# BTN7971b.net
KiCad netlist of a schematic drawn in Altium Designer
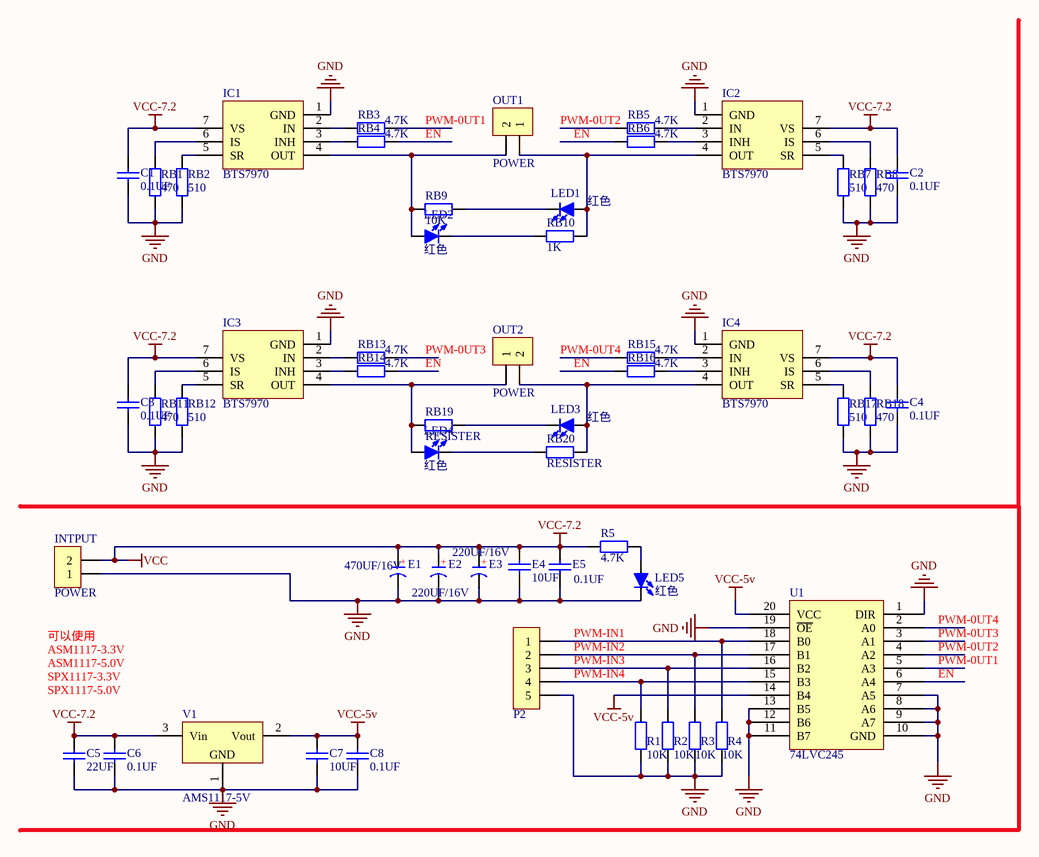
[diagram p0: BTN7971b.SchDoc]

(export (version "E")
  (design (tool "Eeschema 10.0.6"))
  (components
    (comp (ref "C1") (value "0.1UF") (footprint "R/C 0805") (libsource (lib "Schlib1") (part "CAP")))
    (comp (ref "C2") (value "0.1UF") (footprint "R/C 0805") (libsource (lib "Schlib1") (part "CAP")))
    (comp (ref "C3") (value "0.1UF") (footprint "R/C 0805") (libsource (lib "Schlib1") (part "CAP")))
    (comp (ref "C4") (value "0.1UF") (footprint "R/C 0805") (libsource (lib "Schlib1") (part "CAP")))
    (comp (ref "C5") (value "22UF") (footprint "R/C 0805") (libsource (lib "Schlib1") (part "CAP")))
    (comp (ref "C6") (value "0.1UF") (footprint "R/C 0805") (libsource (lib "Schlib1") (part "CAP")))
    (comp (ref "C7") (value "10UF") (footprint "R/C 0805") (libsource (lib "Schlib1") (part "CAP")))
    (comp (ref "C8") (value "0.1UF") (footprint "R/C 0805") (libsource (lib "Schlib1") (part "CAP")))
    (comp (ref "E1")
      (value "470UF/16V")
      (footprint "CM E(8*10.2)")
      (description "贴片电解电容")
      (fields (field (name "版权归属") "源创客"))
      (libsource (lib "3.1   - 电阻-电容-电感") (part "C-CM"))
    )
    (comp (ref "E2")
      (value "220UF/16V")
      (footprint "CM D(6.3*7.7)")
      (description "贴片电解电容")
      (fields (field (name "版权归属") "源创客"))
      (libsource (lib "3.1   - 电阻-电容-电感") (part "C-CM"))
    )
    (comp (ref "E3")
      (value "220UF/16V")
      (footprint "CM D(6.3*7.7)")
      (description "贴片电解电容")
      (fields (field (name "版权归属") "源创客"))
      (libsource (lib "3.1   - 电阻-电容-电感") (part "C-CM"))
    )
    (comp (ref "E4") (value "10UF") (footprint "R/C 0805") (libsource (lib "Schlib1") (part "CAP")))
    (comp (ref "E5") (value "0.1UF") (footprint "R/C 0805") (libsource (lib "Schlib1") (part "CAP")))
    (comp (ref "IC1")
      (value "BTS7970")
      (footprint "TO263-7A")
      (description "电机驱动芯片")
      (fields (field (name "版权归属") "源创客"))
      (libsource (lib "1.1   - IC芯片") (part "BTS7970"))
    )
    (comp (ref "IC2")
      (value "BTS7970")
      (footprint "TO263-7A")
      (description "电机驱动芯片")
      (fields (field (name "版权归属") "源创客"))
      (libsource (lib "") (part "BTS7970_1"))
    )
    (comp (ref "IC3")
      (value "BTS7970")
      (footprint "TO263-7A")
      (description "电机驱动芯片")
      (fields (field (name "版权归属") "源创客"))
      (libsource (lib "1.1   - IC芯片") (part "BTS7970"))
    )
    (comp (ref "IC4")
      (value "BTS7970")
      (footprint "TO263-7A")
      (description "电机驱动芯片")
      (fields (field (name "版权归属") "源创客"))
      (libsource (lib "") (part "BTS7970_1"))
    )
    (comp (ref "INTPUT") (value "POWER") (footprint "XT30") (libsource (lib "") (part "Header 2 L_2")))
    (comp (ref "LED1")
      (value "红色")
      (footprint "LED 0805R")
      (description "贴片LED")
      (fields (field (name "版权归属") "源创客"))
      (libsource (lib "3.6   - LED") (part "LED-SMD"))
    )
    (comp (ref "LED2")
      (value "红色")
      (footprint "LED 0805R")
      (description "贴片LED")
      (fields (field (name "版权归属") "源创客"))
      (libsource (lib "3.6   - LED") (part "LED-SMD"))
    )
    (comp (ref "LED3")
      (value "红色")
      (footprint "LED 0805R")
      (description "贴片LED")
      (fields (field (name "版权归属") "源创客"))
      (libsource (lib "3.6   - LED") (part "LED-SMD"))
    )
    (comp (ref "LED4")
      (value "红色")
      (footprint "LED 0805R")
      (description "贴片LED")
      (fields (field (name "版权归属") "源创客"))
      (libsource (lib "3.6   - LED") (part "LED-SMD"))
    )
    (comp (ref "LED5")
      (value "红色")
      (footprint "LED 0805R")
      (description "贴片LED")
      (fields (field (name "版权归属") "源创客"))
      (libsource (lib "3.6   - LED") (part "LED-SMD"))
    )
    (comp (ref "OUT1") (value "POWER") (footprint "XT30") (libsource (lib "双路BTN电机驱动") (part "Header 2 L")))
    (comp (ref "OUT2") (value "POWER") (footprint "XT30") (libsource (lib "") (part "Header 2 L_1")))
    (comp (ref "P2")
      (value "HDR-1X5")
      (footprint "XH2.54-LI-5P")
      (description "5P接插件")
      (fields (field (name "版权归属") "源创客"))
      (libsource (lib "4.5   - 接插件-脚距2.54") (part "Header 5"))
    )
    (comp (ref "R1") (value "10K") (footprint "R/C 0805") (libsource (lib "Schlib1") (part "RESISTER")))
    (comp (ref "R2") (value "10K") (footprint "R/C 0805") (libsource (lib "Schlib1") (part "RESISTER")))
    (comp (ref "R3") (value "10K") (footprint "R/C 0805") (libsource (lib "Schlib1") (part "RESISTER")))
    (comp (ref "R4") (value "10K") (footprint "R/C 0805") (libsource (lib "Schlib1") (part "RESISTER")))
    (comp (ref "R5") (value "4.7K") (footprint "R/C 0805") (libsource (lib "") (part "RESISTER_1")))
    (comp (ref "RB1") (value "470") (footprint "R/C 0805") (libsource (lib "Schlib1") (part "RESISTER")))
    (comp (ref "RB2") (value "510") (footprint "R/C 0805") (libsource (lib "Schlib1") (part "RESISTER")))
    (comp (ref "RB3") (value "4.7K") (footprint "R/C 0805") (libsource (lib "") (part "RESISTER_1")))
    (comp (ref "RB4") (value "4.7K") (footprint "R/C 0805") (libsource (lib "") (part "RESISTER_1")))
    (comp (ref "RB5") (value "4.7K") (footprint "R/C 0805") (libsource (lib "") (part "RESISTER_1")))
    (comp (ref "RB6") (value "4.7K") (footprint "R/C 0805") (libsource (lib "") (part "RESISTER_1")))
    (comp (ref "RB7") (value "510") (footprint "R/C 0805") (libsource (lib "Schlib1") (part "RESISTER")))
    (comp (ref "RB8") (value "470") (footprint "R/C 0805") (libsource (lib "Schlib1") (part "RESISTER")))
    (comp (ref "RB9") (value "10K") (footprint "R/C 0805") (libsource (lib "") (part "RESISTER_2")))
    (comp (ref "RB10") (value "1K") (footprint "R/C 0805") (libsource (lib "") (part "RESISTER_2")))
    (comp (ref "RB11") (value "470") (footprint "R/C 0805") (libsource (lib "Schlib1") (part "RESISTER")))
    (comp (ref "RB12") (value "510") (footprint "R/C 0805") (libsource (lib "Schlib1") (part "RESISTER")))
    (comp (ref "RB13") (value "4.7K") (footprint "R/C 0805") (libsource (lib "") (part "RESISTER_1")))
    (comp (ref "RB14") (value "4.7K") (footprint "R/C 0805") (libsource (lib "") (part "RESISTER_1")))
    (comp (ref "RB15") (value "4.7K") (footprint "R/C 0805") (libsource (lib "") (part "RESISTER_1")))
    (comp (ref "RB16") (value "4.7K") (footprint "R/C 0805") (libsource (lib "") (part "RESISTER_1")))
    (comp (ref "RB17") (value "510") (footprint "R/C 0805") (libsource (lib "Schlib1") (part "RESISTER")))
    (comp (ref "RB18") (value "470") (footprint "R/C 0805") (libsource (lib "Schlib1") (part "RESISTER")))
    (comp (ref "RB19") (value "RESISTER") (footprint "R/C 0805") (libsource (lib "") (part "RESISTER_2")))
    (comp (ref "RB20") (value "RESISTER") (footprint "R/C 0805") (libsource (lib "") (part "RESISTER_2")))
    (comp (ref "U1") (value "74LVC245") (footprint "SOP-16") (libsource (lib "Schlib1") (part "74LVC245")))
    (comp (ref "V1")
      (value "AMS1117-5V")
      (footprint "SOT223_N")
      (description "三端稳压芯片")
      (fields (field (name "版权归属") "源创客"))
      (libsource (lib "1.3   - 电源类芯片") (part "AMS1117"))
    )
  )
  (nets
    (net (code "1") (name "/EN") (class "Default")
      (node (ref "RB14") (pin "1") (pinfunction "1_1") (pintype "passive"))
      (node (ref "RB16") (pin "2") (pinfunction "2_2") (pintype "passive"))
      (node (ref "RB4") (pin "1") (pinfunction "1_1") (pintype "passive"))
      (node (ref "RB6") (pin "2") (pinfunction "2_2") (pintype "passive"))
      (node (ref "U1") (pin "6") (pinfunction "A4_6") (pintype "passive"))
    )
    (net (code "2") (name "/PWM-0UT1") (class "Default")
      (node (ref "RB3") (pin "1") (pinfunction "1_1") (pintype "passive"))
      (node (ref "U1") (pin "5") (pinfunction "A3_5") (pintype "passive"))
    )
    (net (code "3") (name "/PWM-0UT2") (class "Default")
      (node (ref "RB5") (pin "2") (pinfunction "2_2") (pintype "passive"))
      (node (ref "U1") (pin "4") (pinfunction "A2_4") (pintype "passive"))
    )
    (net (code "4") (name "/PWM-0UT3") (class "Default")
      (node (ref "RB13") (pin "1") (pinfunction "1_1") (pintype "passive"))
      (node (ref "U1") (pin "3") (pinfunction "A1_3") (pintype "passive"))
    )
    (net (code "5") (name "/PWM-0UT4") (class "Default")
      (node (ref "RB15") (pin "2") (pinfunction "2_2") (pintype "passive"))
      (node (ref "U1") (pin "2") (pinfunction "A0_2") (pintype "passive"))
    )
    (net (code "6") (name "/PWM-IN1") (class "Default")
      (node (ref "P2") (pin "1") (pinfunction "1_1") (pintype "passive"))
      (node (ref "R4") (pin "2") (pinfunction "2_2") (pintype "passive"))
      (node (ref "U1") (pin "18") (pinfunction "B0_18") (pintype "passive"))
    )
    (net (code "7") (name "/PWM-IN2") (class "Default")
      (node (ref "P2") (pin "2") (pinfunction "2_2") (pintype "passive"))
      (node (ref "R3") (pin "2") (pinfunction "2_2") (pintype "passive"))
      (node (ref "U1") (pin "17") (pinfunction "B1_17") (pintype "passive"))
    )
    (net (code "8") (name "/PWM-IN3") (class "Default")
      (node (ref "P2") (pin "3") (pinfunction "3_3") (pintype "passive"))
      (node (ref "R2") (pin "2") (pinfunction "2_2") (pintype "passive"))
      (node (ref "U1") (pin "16") (pinfunction "B2_16") (pintype "passive"))
    )
    (net (code "9") (name "/PWM-IN4") (class "Default")
      (node (ref "P2") (pin "4") (pinfunction "4_4") (pintype "passive"))
      (node (ref "R1") (pin "2") (pinfunction "2_2") (pintype "passive"))
      (node (ref "U1") (pin "15") (pinfunction "B3_15") (pintype "passive"))
    )
    (net (code "10") (name "GND") (class "Default")
      (node (ref "C1") (pin "1") (pinfunction "1_1") (pintype "passive"))
      (node (ref "C2") (pin "1") (pinfunction "1_1") (pintype "passive"))
      (node (ref "C3") (pin "1") (pinfunction "1_1") (pintype "passive"))
      (node (ref "C4") (pin "1") (pinfunction "1_1") (pintype "passive"))
      (node (ref "C5") (pin "1") (pinfunction "1_1") (pintype "passive"))
      (node (ref "C6") (pin "1") (pinfunction "1_1") (pintype "passive"))
      (node (ref "C7") (pin "1") (pinfunction "1_1") (pintype "passive"))
      (node (ref "C8") (pin "1") (pinfunction "1_1") (pintype "passive"))
      (node (ref "E1") (pin "2") (pinfunction "K_2") (pintype "passive"))
      (node (ref "E2") (pin "2") (pinfunction "K_2") (pintype "passive"))
      (node (ref "E3") (pin "2") (pinfunction "K_2") (pintype "passive"))
      (node (ref "E4") (pin "1") (pinfunction "1_1") (pintype "passive"))
      (node (ref "E5") (pin "1") (pinfunction "1_1") (pintype "passive"))
      (node (ref "IC1") (pin "1") (pinfunction "GND_1") (pintype "power_in"))
      (node (ref "IC2") (pin "1") (pinfunction "GND_1") (pintype "power_in"))
      (node (ref "IC3") (pin "1") (pinfunction "GND_1") (pintype "power_in"))
      (node (ref "IC4") (pin "1") (pinfunction "GND_1") (pintype "power_in"))
      (node (ref "INTPUT") (pin "1") (pinfunction "1_1") (pintype "passive"))
      (node (ref "LED5") (pin "2") (pinfunction "K_2") (pintype "passive"))
      (node (ref "P2") (pin "5") (pinfunction "5_5") (pintype "passive"))
      (node (ref "R1") (pin "1") (pinfunction "1_1") (pintype "passive"))
      (node (ref "R2") (pin "1") (pinfunction "1_1") (pintype "passive"))
      (node (ref "R3") (pin "1") (pinfunction "1_1") (pintype "passive"))
      (node (ref "R4") (pin "1") (pinfunction "1_1") (pintype "passive"))
      (node (ref "RB1") (pin "1") (pinfunction "1_1") (pintype "passive"))
      (node (ref "RB11") (pin "1") (pinfunction "1_1") (pintype "passive"))
      (node (ref "RB12") (pin "1") (pinfunction "1_1") (pintype "passive"))
      (node (ref "RB17") (pin "1") (pinfunction "1_1") (pintype "passive"))
      (node (ref "RB18") (pin "1") (pinfunction "1_1") (pintype "passive"))
      (node (ref "RB2") (pin "1") (pinfunction "1_1") (pintype "passive"))
      (node (ref "RB7") (pin "1") (pinfunction "1_1") (pintype "passive"))
      (node (ref "RB8") (pin "1") (pinfunction "1_1") (pintype "passive"))
      (node (ref "U1") (pin "1") (pinfunction "DIR_1") (pintype "passive"))
      (node (ref "U1") (pin "10") (pinfunction "GND_10") (pintype "passive"))
      (node (ref "U1") (pin "11") (pinfunction "B7_11") (pintype "passive"))
      (node (ref "U1") (pin "12") (pinfunction "B6_12") (pintype "passive"))
      (node (ref "U1") (pin "13") (pinfunction "B5_13") (pintype "passive"))
      (node (ref "U1") (pin "19") (pinfunction "~{OE}_19") (pintype "passive"))
      (node (ref "U1") (pin "7") (pinfunction "A5_7") (pintype "passive"))
      (node (ref "U1") (pin "8") (pinfunction "A6_8") (pintype "passive"))
      (node (ref "U1") (pin "9") (pinfunction "A7_9") (pintype "passive"))
      (node (ref "V1") (pin "1") (pinfunction "GND_1") (pintype "passive"))
    )
    (net (code "11") (name "Net-(IC1-IN)") (class "Default")
      (node (ref "IC1") (pin "2") (pinfunction "IN_2") (pintype "power_in"))
      (node (ref "RB3") (pin "2") (pinfunction "2_2") (pintype "passive"))
    )
    (net (code "12") (name "Net-(IC1-INH)") (class "Default")
      (node (ref "IC1") (pin "3") (pinfunction "INH_3") (pintype "power_in"))
      (node (ref "RB4") (pin "2") (pinfunction "2_2") (pintype "passive"))
    )
    (net (code "13") (name "Net-(IC1-IS)") (class "Default")
      (node (ref "IC1") (pin "6") (pinfunction "IS_6") (pintype "power_in"))
      (node (ref "RB1") (pin "2") (pinfunction "2_2") (pintype "passive"))
    )
    (net (code "14") (name "Net-(IC1-OUT)") (class "Default")
      (node (ref "IC1") (pin "4") (pinfunction "OUT_4") (pintype "power_in"))
      (node (ref "LED2") (pin "1") (pinfunction "A_1") (pintype "passive"))
      (node (ref "OUT1") (pin "2") (pinfunction "2_2") (pintype "passive"))
      (node (ref "RB9") (pin "1") (pinfunction "1_1") (pintype "passive"))
    )
    (net (code "15") (name "Net-(IC1-SR)") (class "Default")
      (node (ref "IC1") (pin "5") (pinfunction "SR_5") (pintype "power_in"))
      (node (ref "RB2") (pin "2") (pinfunction "2_2") (pintype "passive"))
    )
    (net (code "16") (name "Net-(IC2-IN)") (class "Default")
      (node (ref "IC2") (pin "2") (pinfunction "IN_2") (pintype "power_in"))
      (node (ref "RB5") (pin "1") (pinfunction "1_1") (pintype "passive"))
    )
    (net (code "17") (name "Net-(IC2-INH)") (class "Default")
      (node (ref "IC2") (pin "3") (pinfunction "INH_3") (pintype "power_in"))
      (node (ref "RB6") (pin "1") (pinfunction "1_1") (pintype "passive"))
    )
    (net (code "18") (name "Net-(IC2-IS)") (class "Default")
      (node (ref "IC2") (pin "6") (pinfunction "IS_6") (pintype "power_in"))
      (node (ref "RB8") (pin "2") (pinfunction "2_2") (pintype "passive"))
    )
    (net (code "19") (name "Net-(IC2-OUT)") (class "Default")
      (node (ref "IC2") (pin "4") (pinfunction "OUT_4") (pintype "power_in"))
      (node (ref "LED1") (pin "1") (pinfunction "A_1") (pintype "passive"))
      (node (ref "OUT1") (pin "1") (pinfunction "1_1") (pintype "passive"))
      (node (ref "RB10") (pin "2") (pinfunction "2_2") (pintype "passive"))
    )
    (net (code "20") (name "Net-(IC2-SR)") (class "Default")
      (node (ref "IC2") (pin "5") (pinfunction "SR_5") (pintype "power_in"))
      (node (ref "RB7") (pin "2") (pinfunction "2_2") (pintype "passive"))
    )
    (net (code "21") (name "Net-(IC3-IN)") (class "Default")
      (node (ref "IC3") (pin "2") (pinfunction "IN_2") (pintype "power_in"))
      (node (ref "RB13") (pin "2") (pinfunction "2_2") (pintype "passive"))
    )
    (net (code "22") (name "Net-(IC3-INH)") (class "Default")
      (node (ref "IC3") (pin "3") (pinfunction "INH_3") (pintype "power_in"))
      (node (ref "RB14") (pin "2") (pinfunction "2_2") (pintype "passive"))
    )
    (net (code "23") (name "Net-(IC3-IS)") (class "Default")
      (node (ref "IC3") (pin "6") (pinfunction "IS_6") (pintype "power_in"))
      (node (ref "RB11") (pin "2") (pinfunction "2_2") (pintype "passive"))
    )
    (net (code "24") (name "Net-(IC3-OUT)") (class "Default")
      (node (ref "IC3") (pin "4") (pinfunction "OUT_4") (pintype "power_in"))
      (node (ref "LED4") (pin "1") (pinfunction "A_1") (pintype "passive"))
      (node (ref "OUT2") (pin "1") (pinfunction "1_1") (pintype "passive"))
      (node (ref "RB19") (pin "1") (pinfunction "1_1") (pintype "passive"))
    )
    (net (code "25") (name "Net-(IC3-SR)") (class "Default")
      (node (ref "IC3") (pin "5") (pinfunction "SR_5") (pintype "power_in"))
      (node (ref "RB12") (pin "2") (pinfunction "2_2") (pintype "passive"))
    )
    (net (code "26") (name "Net-(IC4-IN)") (class "Default")
      (node (ref "IC4") (pin "2") (pinfunction "IN_2") (pintype "power_in"))
      (node (ref "RB15") (pin "1") (pinfunction "1_1") (pintype "passive"))
    )
    (net (code "27") (name "Net-(IC4-INH)") (class "Default")
      (node (ref "IC4") (pin "3") (pinfunction "INH_3") (pintype "power_in"))
      (node (ref "RB16") (pin "1") (pinfunction "1_1") (pintype "passive"))
    )
    (net (code "28") (name "Net-(IC4-IS)") (class "Default")
      (node (ref "IC4") (pin "6") (pinfunction "IS_6") (pintype "power_in"))
      (node (ref "RB18") (pin "2") (pinfunction "2_2") (pintype "passive"))
    )
    (net (code "29") (name "Net-(IC4-OUT)") (class "Default")
      (node (ref "IC4") (pin "4") (pinfunction "OUT_4") (pintype "power_in"))
      (node (ref "LED3") (pin "1") (pinfunction "A_1") (pintype "passive"))
      (node (ref "OUT2") (pin "2") (pinfunction "2_2") (pintype "passive"))
      (node (ref "RB20") (pin "2") (pinfunction "2_2") (pintype "passive"))
    )
    (net (code "30") (name "Net-(IC4-SR)") (class "Default")
      (node (ref "IC4") (pin "5") (pinfunction "SR_5") (pintype "power_in"))
      (node (ref "RB17") (pin "2") (pinfunction "2_2") (pintype "passive"))
    )
    (net (code "31") (name "Net-(LED1-K)") (class "Default")
      (node (ref "LED1") (pin "2") (pinfunction "K_2") (pintype "passive"))
      (node (ref "RB9") (pin "2") (pinfunction "2_2") (pintype "passive"))
    )
    (net (code "32") (name "Net-(LED2-K)") (class "Default")
      (node (ref "LED2") (pin "2") (pinfunction "K_2") (pintype "passive"))
      (node (ref "RB10") (pin "1") (pinfunction "1_1") (pintype "passive"))
    )
    (net (code "33") (name "Net-(LED3-K)") (class "Default")
      (node (ref "LED3") (pin "2") (pinfunction "K_2") (pintype "passive"))
      (node (ref "RB19") (pin "2") (pinfunction "2_2") (pintype "passive"))
    )
    (net (code "34") (name "Net-(LED4-K)") (class "Default")
      (node (ref "LED4") (pin "2") (pinfunction "K_2") (pintype "passive"))
      (node (ref "RB20") (pin "1") (pinfunction "1_1") (pintype "passive"))
    )
    (net (code "35") (name "Net-(LED5-A)") (class "Default")
      (node (ref "LED5") (pin "1") (pinfunction "A_1") (pintype "passive"))
      (node (ref "R5") (pin "1") (pinfunction "1_1") (pintype "passive"))
    )
    (net (code "36") (name "VCC") (class "Default")
      (node (ref "C1") (pin "2") (pinfunction "2_2") (pintype "passive"))
      (node (ref "C2") (pin "2") (pinfunction "2_2") (pintype "passive"))
      (node (ref "C3") (pin "2") (pinfunction "2_2") (pintype "passive"))
      (node (ref "C4") (pin "2") (pinfunction "2_2") (pintype "passive"))
      (node (ref "C5") (pin "2") (pinfunction "2_2") (pintype "passive"))
      (node (ref "C6") (pin "2") (pinfunction "2_2") (pintype "passive"))
      (node (ref "E1") (pin "1") (pinfunction "A_1") (pintype "passive"))
      (node (ref "E2") (pin "1") (pinfunction "A_1") (pintype "passive"))
      (node (ref "E3") (pin "1") (pinfunction "A_1") (pintype "passive"))
      (node (ref "E4") (pin "2") (pinfunction "2_2") (pintype "passive"))
      (node (ref "E5") (pin "2") (pinfunction "2_2") (pintype "passive"))
      (node (ref "IC1") (pin "7") (pinfunction "VS_7") (pintype "power_in"))
      (node (ref "IC2") (pin "7") (pinfunction "VS_7") (pintype "power_in"))
      (node (ref "IC3") (pin "7") (pinfunction "VS_7") (pintype "power_in"))
      (node (ref "IC4") (pin "7") (pinfunction "VS_7") (pintype "power_in"))
      (node (ref "INTPUT") (pin "2") (pinfunction "2_2") (pintype "passive"))
      (node (ref "R5") (pin "2") (pinfunction "2_2") (pintype "passive"))
      (node (ref "V1") (pin "3") (pinfunction "Vin_3") (pintype "passive"))
    )
    (net (code "37") (name "VCC-5v") (class "Default")
      (node (ref "C7") (pin "2") (pinfunction "2_2") (pintype "passive"))
      (node (ref "C8") (pin "2") (pinfunction "2_2") (pintype "passive"))
      (node (ref "U1") (pin "14") (pinfunction "B4_14") (pintype "passive"))
      (node (ref "U1") (pin "20") (pinfunction "VCC_20") (pintype "passive"))
      (node (ref "V1") (pin "2") (pinfunction "Vout_2") (pintype "passive"))
    )
  )
)
